# arduino-dust-density-meter.net
KiCad netlist of a schematic drawn in EAGLE
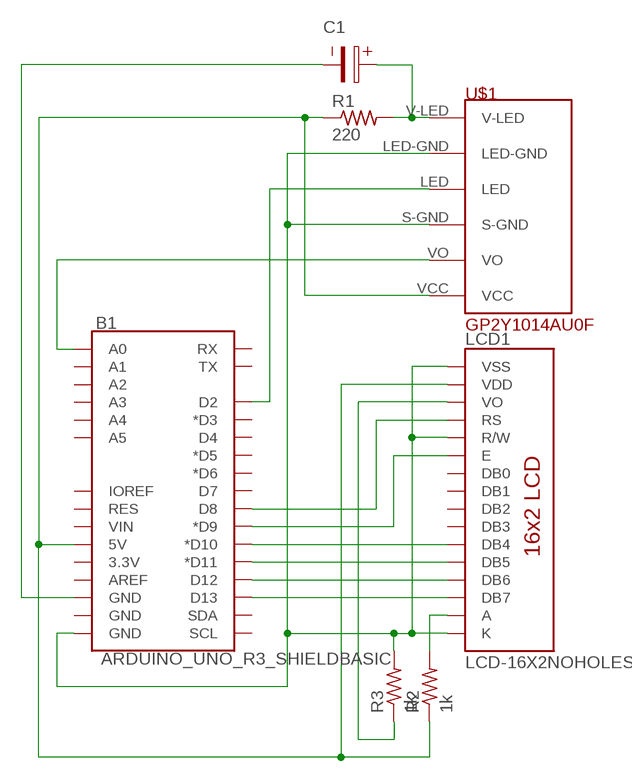
[diagram p0: schematic, sheet 1]

(export (version "E")
  (design (tool "Eeschema 10.0.6"))
  (components
    (comp (ref "B1")
      (value "ARDUINO_UNO_R3_SHIELDBASIC")
      (footprint "eagle-import:UNO_R3_SHIELD")
      (libsource (lib "eagle-import") (part "ARDUINO_UNO_R3_SHIELDBASIC"))
    )
    (comp (ref "C1")
      (value "WCAP-PTG5_10X12,5_870025575007")
      (footprint "eagle-import:10X5X0.9(DXAXB)")
      (libsource (lib "eagle-import") (part "WCAP-PTG5_870025575007_10X12,5"))
    )
    (comp (ref "LCD1")
      (value "LCD-16X2NOHOLES")
      (footprint "eagle-import:LCD-16X2_NOHOLESNOSILK")
      (libsource (lib "eagle-import") (part "LCD-16X2NOHOLES"))
    )
    (comp (ref "R1")
      (value "220")
      (footprint "eagle-import:0309_12")
      (libsource (lib "eagle-import") (part "R-US_0309/12"))
    )
    (comp (ref "R2")
      (value "1k")
      (footprint "eagle-import:0309_12")
      (libsource (lib "eagle-import") (part "R-US_0309/12"))
    )
    (comp (ref "R3")
      (value "1k")
      (footprint "eagle-import:0309_12")
      (libsource (lib "eagle-import") (part "R-US_0309/12"))
    )
    (comp (ref "U$1")
      (value "GP2Y1014AU0F")
      (footprint "eagle-import:GP2Y1014AU0F")
      (libsource (lib "eagle-import") (part "GP2Y1014AU0F"))
    )
  )
  (nets
    (net (code "1") (name "Net-(B1-*D9)") (class "Default")
      (node (ref "B1") (pin "D9") (pinfunction "*D9_D9") (pintype "bidirectional"))
      (node (ref "LCD1") (pin "6") (pinfunction "E_6") (pintype "input"))
    )
    (net (code "2") (name "Net-(B1-*D10)") (class "Default")
      (node (ref "B1") (pin "D10") (pinfunction "*D10_D10") (pintype "bidirectional"))
      (node (ref "LCD1") (pin "11") (pinfunction "DB4_11") (pintype "bidirectional"))
    )
    (net (code "3") (name "Net-(B1-*D11)") (class "Default")
      (node (ref "B1") (pin "D11") (pinfunction "*D11_D11") (pintype "bidirectional"))
      (node (ref "LCD1") (pin "12") (pinfunction "DB5_12") (pintype "bidirectional"))
    )
    (net (code "4") (name "Net-(B1-GND-PadGND@2)") (class "Default")
      (node (ref "B1") (pin "GND@2") (pinfunction "GND_GND@2") (pintype "bidirectional"))
      (node (ref "C1") (pin "2") (pinfunction "2_2") (pintype "passive"))
    )
    (net (code "5") (name "Net-(B1-PadA0)") (class "Default")
      (node (ref "B1") (pin "A0") (pinfunction "A0_A0") (pintype "bidirectional"))
      (node (ref "U$1") (pin "VO") (pinfunction "VO_VO") (pintype "bidirectional"))
    )
    (net (code "6") (name "Net-(B1-PadD2)") (class "Default")
      (node (ref "B1") (pin "D2") (pinfunction "D2_D2") (pintype "bidirectional"))
      (node (ref "U$1") (pin "LED") (pinfunction "LED_LED") (pintype "bidirectional"))
    )
    (net (code "7") (name "Net-(C1-Pad1)") (class "Default")
      (node (ref "C1") (pin "1") (pinfunction "1_1") (pintype "passive"))
      (node (ref "R1") (pin "2") (pinfunction "2_2") (pintype "passive"))
      (node (ref "U$1") (pin "V-LED") (pinfunction "V-LED_V-LED") (pintype "bidirectional"))
    )
    (net (code "8") (name "Net-(LCD1-A)") (class "Default")
      (node (ref "LCD1") (pin "15") (pinfunction "A_15") (pintype "power_in"))
      (node (ref "R2") (pin "2") (pinfunction "2_2") (pintype "passive"))
    )
    (net (code "9") (name "Net-(LCD1-DB6)") (class "Default")
      (node (ref "B1") (pin "D12") (pinfunction "D12_D12") (pintype "bidirectional"))
      (node (ref "LCD1") (pin "13") (pinfunction "DB6_13") (pintype "bidirectional"))
    )
    (net (code "10") (name "Net-(LCD1-DB7)") (class "Default")
      (node (ref "B1") (pin "D13") (pinfunction "D13_D13") (pintype "bidirectional"))
      (node (ref "LCD1") (pin "14") (pinfunction "DB7_14") (pintype "bidirectional"))
    )
    (net (code "11") (name "Net-(LCD1-K)") (class "Default")
      (node (ref "B1") (pin "GND@0") (pinfunction "GND_GND@0") (pintype "bidirectional"))
      (node (ref "LCD1") (pin "1") (pinfunction "VSS_1") (pintype "power_in"))
      (node (ref "LCD1") (pin "16") (pinfunction "K_16") (pintype "power_in"))
      (node (ref "LCD1") (pin "5") (pinfunction "R/W_5") (pintype "input"))
      (node (ref "R3") (pin "2") (pinfunction "2_2") (pintype "passive"))
      (node (ref "U$1") (pin "LED-GND") (pinfunction "LED-GND_LED-GND") (pintype "bidirectional"))
      (node (ref "U$1") (pin "S-GND") (pinfunction "S-GND_S-GND") (pintype "bidirectional"))
    )
    (net (code "12") (name "Net-(LCD1-RS)") (class "Default")
      (node (ref "B1") (pin "D8") (pinfunction "D8_D8") (pintype "bidirectional"))
      (node (ref "LCD1") (pin "4") (pinfunction "RS_4") (pintype "input"))
    )
    (net (code "13") (name "Net-(LCD1-VDD)") (class "Default")
      (node (ref "B1") (pin "5V") (pinfunction "5V_5V") (pintype "bidirectional"))
      (node (ref "LCD1") (pin "2") (pinfunction "VDD_2") (pintype "power_in"))
      (node (ref "R1") (pin "1") (pinfunction "1_1") (pintype "passive"))
      (node (ref "R2") (pin "1") (pinfunction "1_1") (pintype "passive"))
      (node (ref "U$1") (pin "VCC") (pinfunction "VCC_VCC") (pintype "bidirectional"))
    )
    (net (code "14") (name "Net-(LCD1-VO)") (class "Default")
      (node (ref "LCD1") (pin "3") (pinfunction "VO_3") (pintype "bidirectional"))
      (node (ref "R3") (pin "1") (pinfunction "1_1") (pintype "passive"))
    )
    (net (code "15") (name "unconnected-(B1-*D3-PadD3)") (class "Default")
      (node (ref "B1") (pin "D3") (pinfunction "*D3_D3") (pintype "bidirectional"))
    )
    (net (code "16") (name "unconnected-(B1-*D5-PadD5)") (class "Default")
      (node (ref "B1") (pin "D5") (pinfunction "*D5_D5") (pintype "bidirectional"))
    )
    (net (code "17") (name "unconnected-(B1-*D6-PadD6)") (class "Default")
      (node (ref "B1") (pin "D6") (pinfunction "*D6_D6") (pintype "bidirectional"))
    )
    (net (code "18") (name "unconnected-(B1-GND-PadGND@1)") (class "Default")
      (node (ref "B1") (pin "GND@1") (pinfunction "GND_GND@1") (pintype "bidirectional"))
    )
    (net (code "19") (name "unconnected-(B1-Pad3.3V)") (class "Default")
      (node (ref "B1") (pin "3.3V") (pinfunction "3.3V_3.3V") (pintype "bidirectional"))
    )
    (net (code "20") (name "unconnected-(B1-PadA1)") (class "Default")
      (node (ref "B1") (pin "A1") (pinfunction "A1_A1") (pintype "bidirectional"))
    )
    (net (code "21") (name "unconnected-(B1-PadA2)") (class "Default")
      (node (ref "B1") (pin "A2") (pinfunction "A2_A2") (pintype "bidirectional"))
    )
    (net (code "22") (name "unconnected-(B1-PadA3)") (class "Default")
      (node (ref "B1") (pin "A3") (pinfunction "A3_A3") (pintype "bidirectional"))
    )
    (net (code "23") (name "unconnected-(B1-PadA4)") (class "Default")
      (node (ref "B1") (pin "A4") (pinfunction "A4_A4") (pintype "bidirectional"))
    )
    (net (code "24") (name "unconnected-(B1-PadA5)") (class "Default")
      (node (ref "B1") (pin "A5") (pinfunction "A5_A5") (pintype "bidirectional"))
    )
    (net (code "25") (name "unconnected-(B1-PadAREF)") (class "Default")
      (node (ref "B1") (pin "AREF") (pinfunction "AREF_AREF") (pintype "bidirectional"))
    )
    (net (code "26") (name "unconnected-(B1-PadD4)") (class "Default")
      (node (ref "B1") (pin "D4") (pinfunction "D4_D4") (pintype "bidirectional"))
    )
    (net (code "27") (name "unconnected-(B1-PadD7)") (class "Default")
      (node (ref "B1") (pin "D7") (pinfunction "D7_D7") (pintype "bidirectional"))
    )
    (net (code "28") (name "unconnected-(B1-PadIOREF)") (class "Default")
      (node (ref "B1") (pin "IOREF") (pinfunction "IOREF_IOREF") (pintype "bidirectional"))
    )
    (net (code "29") (name "unconnected-(B1-PadRES)") (class "Default")
      (node (ref "B1") (pin "RES") (pinfunction "RES_RES") (pintype "bidirectional"))
    )
    (net (code "30") (name "unconnected-(B1-PadRX)") (class "Default")
      (node (ref "B1") (pin "RX") (pinfunction "RX_RX") (pintype "bidirectional"))
    )
    (net (code "31") (name "unconnected-(B1-PadSCL)") (class "Default")
      (node (ref "B1") (pin "SCL") (pinfunction "SCL_SCL") (pintype "bidirectional"))
    )
    (net (code "32") (name "unconnected-(B1-PadSDA)") (class "Default")
      (node (ref "B1") (pin "SDA") (pinfunction "SDA_SDA") (pintype "bidirectional"))
    )
    (net (code "33") (name "unconnected-(B1-PadTX)") (class "Default")
      (node (ref "B1") (pin "TX") (pinfunction "TX_TX") (pintype "bidirectional"))
    )
    (net (code "34") (name "unconnected-(B1-PadVIN)") (class "Default")
      (node (ref "B1") (pin "VIN") (pinfunction "VIN_VIN") (pintype "bidirectional"))
    )
    (net (code "35") (name "unconnected-(LCD1-DB0-Pad7)") (class "Default")
      (node (ref "LCD1") (pin "7") (pinfunction "DB0_7") (pintype "bidirectional"))
    )
    (net (code "36") (name "unconnected-(LCD1-DB1-Pad8)") (class "Default")
      (node (ref "LCD1") (pin "8") (pinfunction "DB1_8") (pintype "bidirectional"))
    )
    (net (code "37") (name "unconnected-(LCD1-DB2-Pad9)") (class "Default")
      (node (ref "LCD1") (pin "9") (pinfunction "DB2_9") (pintype "bidirectional"))
    )
    (net (code "38") (name "unconnected-(LCD1-DB3-Pad10)") (class "Default")
      (node (ref "LCD1") (pin "10") (pinfunction "DB3_10") (pintype "bidirectional"))
    )
  )
)
